# blink1mk3_005t5a.net
KiCad netlist of a schematic drawn in EAGLE
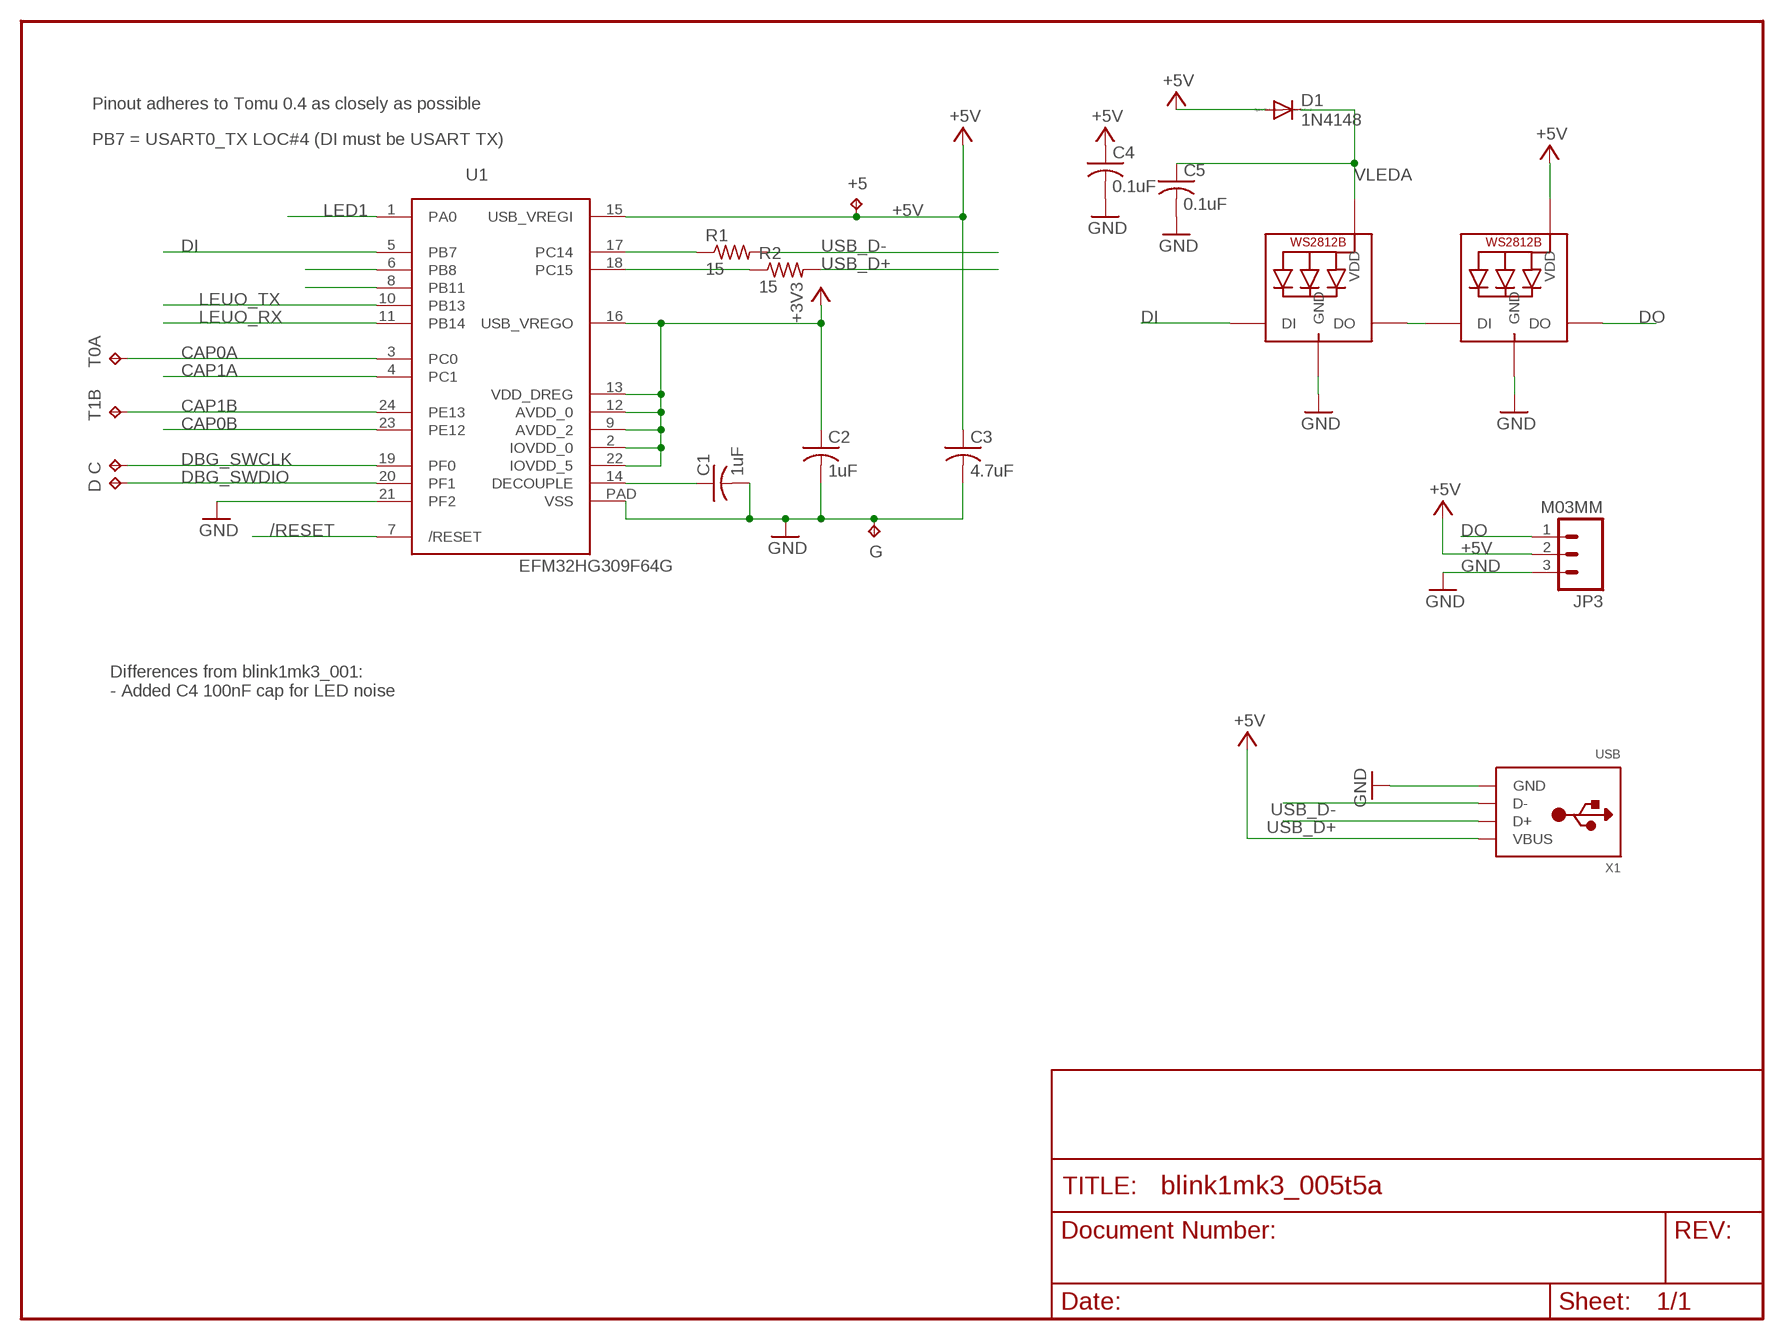
[diagram p0: schematic, sheet 1]

(export (version "E")
  (design (tool "Eeschema 10.0.6"))
  (components
    (comp (ref "+5")
      (value "TPTP10R")
      (footprint "eagle-import:TP10R")
      (libsource (lib "eagle-import") (part "TPTP10R"))
    )
    (comp (ref "C")
      (value "TPTP10R")
      (footprint "eagle-import:TP10R")
      (libsource (lib "eagle-import") (part "TPTP10R"))
    )
    (comp (ref "C1")
      (value "1uF")
      (footprint "eagle-import:C0402")
      (libsource (lib "eagle-import") (part "C-USC0402"))
    )
    (comp (ref "C2")
      (value "1uF")
      (footprint "eagle-import:C0402")
      (libsource (lib "eagle-import") (part "C-USC0402"))
    )
    (comp (ref "C3")
      (value "4.7uF")
      (footprint "eagle-import:C0402")
      (libsource (lib "eagle-import") (part "C-USC0402"))
    )
    (comp (ref "C4")
      (value "0.1uF")
      (footprint "eagle-import:C0402")
      (libsource (lib "eagle-import") (part "C-USC0402"))
    )
    (comp (ref "C5")
      (value "0.1uF")
      (footprint "eagle-import:C0402")
      (libsource (lib "eagle-import") (part "C-USC0402"))
    )
    (comp (ref "D")
      (value "TPTP10R")
      (footprint "eagle-import:TP10R")
      (libsource (lib "eagle-import") (part "TPTP10R"))
    )
    (comp (ref "D1")
      (value "1N4148")
      (footprint "eagle-import:SOD523")
      (libsource (lib "eagle-import") (part "DIODE-SOD523"))
    )
    (comp (ref "G")
      (value "TPTP10R")
      (footprint "eagle-import:TP10R")
      (libsource (lib "eagle-import") (part "TPTP10R"))
    )
    (comp (ref "JP3")
      (value "M03MM")
      (footprint "eagle-import:1X03-1.5MM")
      (libsource (lib "eagle-import") (part "M03MM"))
    )
    (comp (ref "LED1")
      (value "SK6812MINI")
      (footprint "eagle-import:LED3535")
      (libsource (lib "eagle-import") (part "WS2812B3535"))
    )
    (comp (ref "LED2")
      (value "SK6812MINI")
      (footprint "eagle-import:LED3535")
      (libsource (lib "eagle-import") (part "WS2812B3535"))
    )
    (comp (ref "R1")
      (value "15")
      (footprint "eagle-import:R0402")
      (libsource (lib "eagle-import") (part "R-US_R0402"))
    )
    (comp (ref "R2")
      (value "15")
      (footprint "eagle-import:R0402")
      (libsource (lib "eagle-import") (part "R-US_R0402"))
    )
    (comp (ref "T0A")
      (value "TPTP15R")
      (footprint "eagle-import:TP15R")
      (libsource (lib "eagle-import") (part "TPTP15R"))
    )
    (comp (ref "T1B")
      (value "TPTP15R")
      (footprint "eagle-import:TP15R")
      (libsource (lib "eagle-import") (part "TPTP15R"))
    )
    (comp (ref "U1")
      (value "EFM32HG309F64G")
      (footprint "eagle-import:QFN24PAD")
      (libsource (lib "eagle-import") (part "EFM32HG309F64G"))
    )
    (comp (ref "X1")
      (value "USB")
      (footprint "eagle-import:MOLEX-48037-1000")
      (libsource (lib "eagle-import") (part "USB"))
    )
  )
  (nets
    (net (code "1") (name "+3V3") (class "Default")
      (node (ref "C2") (pin "1") (pinfunction "1_1") (pintype "passive"))
      (node (ref "U1") (pin "12") (pinfunction "AVDD_0_12") (pintype "bidirectional"))
      (node (ref "U1") (pin "13") (pinfunction "VDD_DREG_13") (pintype "bidirectional"))
      (node (ref "U1") (pin "16") (pinfunction "USB_VREGO_16") (pintype "bidirectional"))
      (node (ref "U1") (pin "2") (pinfunction "IOVDD_0_2") (pintype "bidirectional"))
      (node (ref "U1") (pin "22") (pinfunction "IOVDD_5_22") (pintype "bidirectional"))
      (node (ref "U1") (pin "9") (pinfunction "AVDD_2_9") (pintype "bidirectional"))
    )
    (net (code "2") (name "+5V") (class "Default")
      (node (ref "+5") (pin "TP") (pinfunction "TP_TP") (pintype "input"))
      (node (ref "C3") (pin "1") (pinfunction "1_1") (pintype "passive"))
      (node (ref "C4") (pin "1") (pinfunction "1_1") (pintype "passive"))
      (node (ref "D1") (pin "A") (pinfunction "A_A") (pintype "passive"))
      (node (ref "JP3") (pin "2") (pinfunction "2_2") (pintype "passive"))
      (node (ref "LED2") (pin "2") (pinfunction "VDD_2") (pintype "power_in"))
      (node (ref "U1") (pin "15") (pinfunction "USB_VREGI_15") (pintype "bidirectional"))
      (node (ref "X1") (pin "1") (pinfunction "VBUS_1") (pintype "power_in"))
    )
    (net (code "3") (name "/CAP0A") (class "Default")
      (node (ref "T0A") (pin "TP") (pinfunction "TP_TP") (pintype "input"))
      (node (ref "U1") (pin "3") (pinfunction "PC0_3") (pintype "bidirectional"))
    )
    (net (code "4") (name "/CAP0B") (class "Default")
      (node (ref "U1") (pin "23") (pinfunction "PE12_23") (pintype "bidirectional"))
    )
    (net (code "5") (name "/CAP1A") (class "Default")
      (node (ref "U1") (pin "4") (pinfunction "PC1_4") (pintype "bidirectional"))
    )
    (net (code "6") (name "/CAP1B") (class "Default")
      (node (ref "T1B") (pin "TP") (pinfunction "TP_TP") (pintype "input"))
      (node (ref "U1") (pin "24") (pinfunction "PE13_24") (pintype "bidirectional"))
    )
    (net (code "7") (name "/DBG_SWCLK") (class "Default")
      (node (ref "C") (pin "TP") (pinfunction "TP_TP") (pintype "input"))
      (node (ref "U1") (pin "19") (pinfunction "PF0_19") (pintype "bidirectional"))
    )
    (net (code "8") (name "/DBG_SWDIO") (class "Default")
      (node (ref "D") (pin "TP") (pinfunction "TP_TP") (pintype "input"))
      (node (ref "U1") (pin "20") (pinfunction "PF1_20") (pintype "bidirectional"))
    )
    (net (code "9") (name "/DI") (class "Default")
      (node (ref "LED1") (pin "1") (pinfunction "DI_1") (pintype "input"))
      (node (ref "U1") (pin "5") (pinfunction "PB7_5") (pintype "bidirectional"))
    )
    (net (code "10") (name "/DO") (class "Default")
      (node (ref "JP3") (pin "1") (pinfunction "1_1") (pintype "passive"))
      (node (ref "LED2") (pin "3") (pinfunction "DO_3") (pintype "output"))
    )
    (net (code "11") (name "/LED1") (class "Default")
      (node (ref "U1") (pin "1") (pinfunction "PA0_1") (pintype "bidirectional"))
    )
    (net (code "12") (name "/LEUO_RX") (class "Default")
      (node (ref "U1") (pin "11") (pinfunction "PB14_11") (pintype "bidirectional"))
    )
    (net (code "13") (name "/LEUO_TX") (class "Default")
      (node (ref "U1") (pin "10") (pinfunction "PB13_10") (pintype "bidirectional"))
    )
    (net (code "14") (name "/USB_D+") (class "Default")
      (node (ref "R2") (pin "2") (pinfunction "2_2") (pintype "passive"))
      (node (ref "X1") (pin "3") (pinfunction "D+_3") (pintype "bidirectional"))
    )
    (net (code "15") (name "/USB_D-") (class "Default")
      (node (ref "R1") (pin "2") (pinfunction "2_2") (pintype "passive"))
      (node (ref "X1") (pin "2") (pinfunction "D-_2") (pintype "bidirectional"))
    )
    (net (code "16") (name "/VLEDA") (class "Default")
      (node (ref "C5") (pin "1") (pinfunction "1_1") (pintype "passive"))
      (node (ref "D1") (pin "C") (pinfunction "C_C") (pintype "passive"))
      (node (ref "LED1") (pin "2") (pinfunction "VDD_2") (pintype "power_in"))
    )
    (net (code "17") (name "/{slash}RESET") (class "Default")
      (node (ref "U1") (pin "7") (pinfunction "/RESET_7") (pintype "bidirectional"))
    )
    (net (code "18") (name "GND") (class "Default")
      (node (ref "C1") (pin "2") (pinfunction "2_2") (pintype "passive"))
      (node (ref "C2") (pin "2") (pinfunction "2_2") (pintype "passive"))
      (node (ref "C3") (pin "2") (pinfunction "2_2") (pintype "passive"))
      (node (ref "C4") (pin "2") (pinfunction "2_2") (pintype "passive"))
      (node (ref "C5") (pin "2") (pinfunction "2_2") (pintype "passive"))
      (node (ref "G") (pin "TP") (pinfunction "TP_TP") (pintype "input"))
      (node (ref "JP3") (pin "3") (pinfunction "3_3") (pintype "passive"))
      (node (ref "LED1") (pin "4") (pinfunction "GND_4") (pintype "power_in"))
      (node (ref "LED2") (pin "4") (pinfunction "GND_4") (pintype "power_in"))
      (node (ref "U1") (pin "21") (pinfunction "PF2_21") (pintype "bidirectional"))
      (node (ref "U1") (pin "PAD") (pinfunction "VSS_PAD") (pintype "bidirectional"))
      (node (ref "X1") (pin "4") (pinfunction "GND_4") (pintype "power_in"))
    )
    (net (code "19") (name "Net-(LED1-DO)") (class "Default")
      (node (ref "LED1") (pin "3") (pinfunction "DO_3") (pintype "output"))
      (node (ref "LED2") (pin "1") (pinfunction "DI_1") (pintype "input"))
    )
    (net (code "20") (name "Net-(U1-DECOUPLE)") (class "Default")
      (node (ref "C1") (pin "1") (pinfunction "1_1") (pintype "passive"))
      (node (ref "U1") (pin "14") (pinfunction "DECOUPLE_14") (pintype "bidirectional"))
    )
    (net (code "21") (name "Net-(U1-PC14)") (class "Default")
      (node (ref "R1") (pin "1") (pinfunction "1_1") (pintype "passive"))
      (node (ref "U1") (pin "17") (pinfunction "PC14_17") (pintype "bidirectional"))
    )
    (net (code "22") (name "Net-(U1-PC15)") (class "Default")
      (node (ref "R2") (pin "1") (pinfunction "1_1") (pintype "passive"))
      (node (ref "U1") (pin "18") (pinfunction "PC15_18") (pintype "bidirectional"))
    )
    (net (code "23") (name "unconnected-(U1-PB8-Pad6)") (class "Default")
      (node (ref "U1") (pin "6") (pinfunction "PB8_6") (pintype "bidirectional"))
    )
    (net (code "24") (name "unconnected-(U1-PB11-Pad8)") (class "Default")
      (node (ref "U1") (pin "8") (pinfunction "PB11_8") (pintype "bidirectional"))
    )
  )
)
